# SCH_BOB_Drivers_4x_2022-07-10.net
KiCad netlist of a schematic drawn in EasyEDA
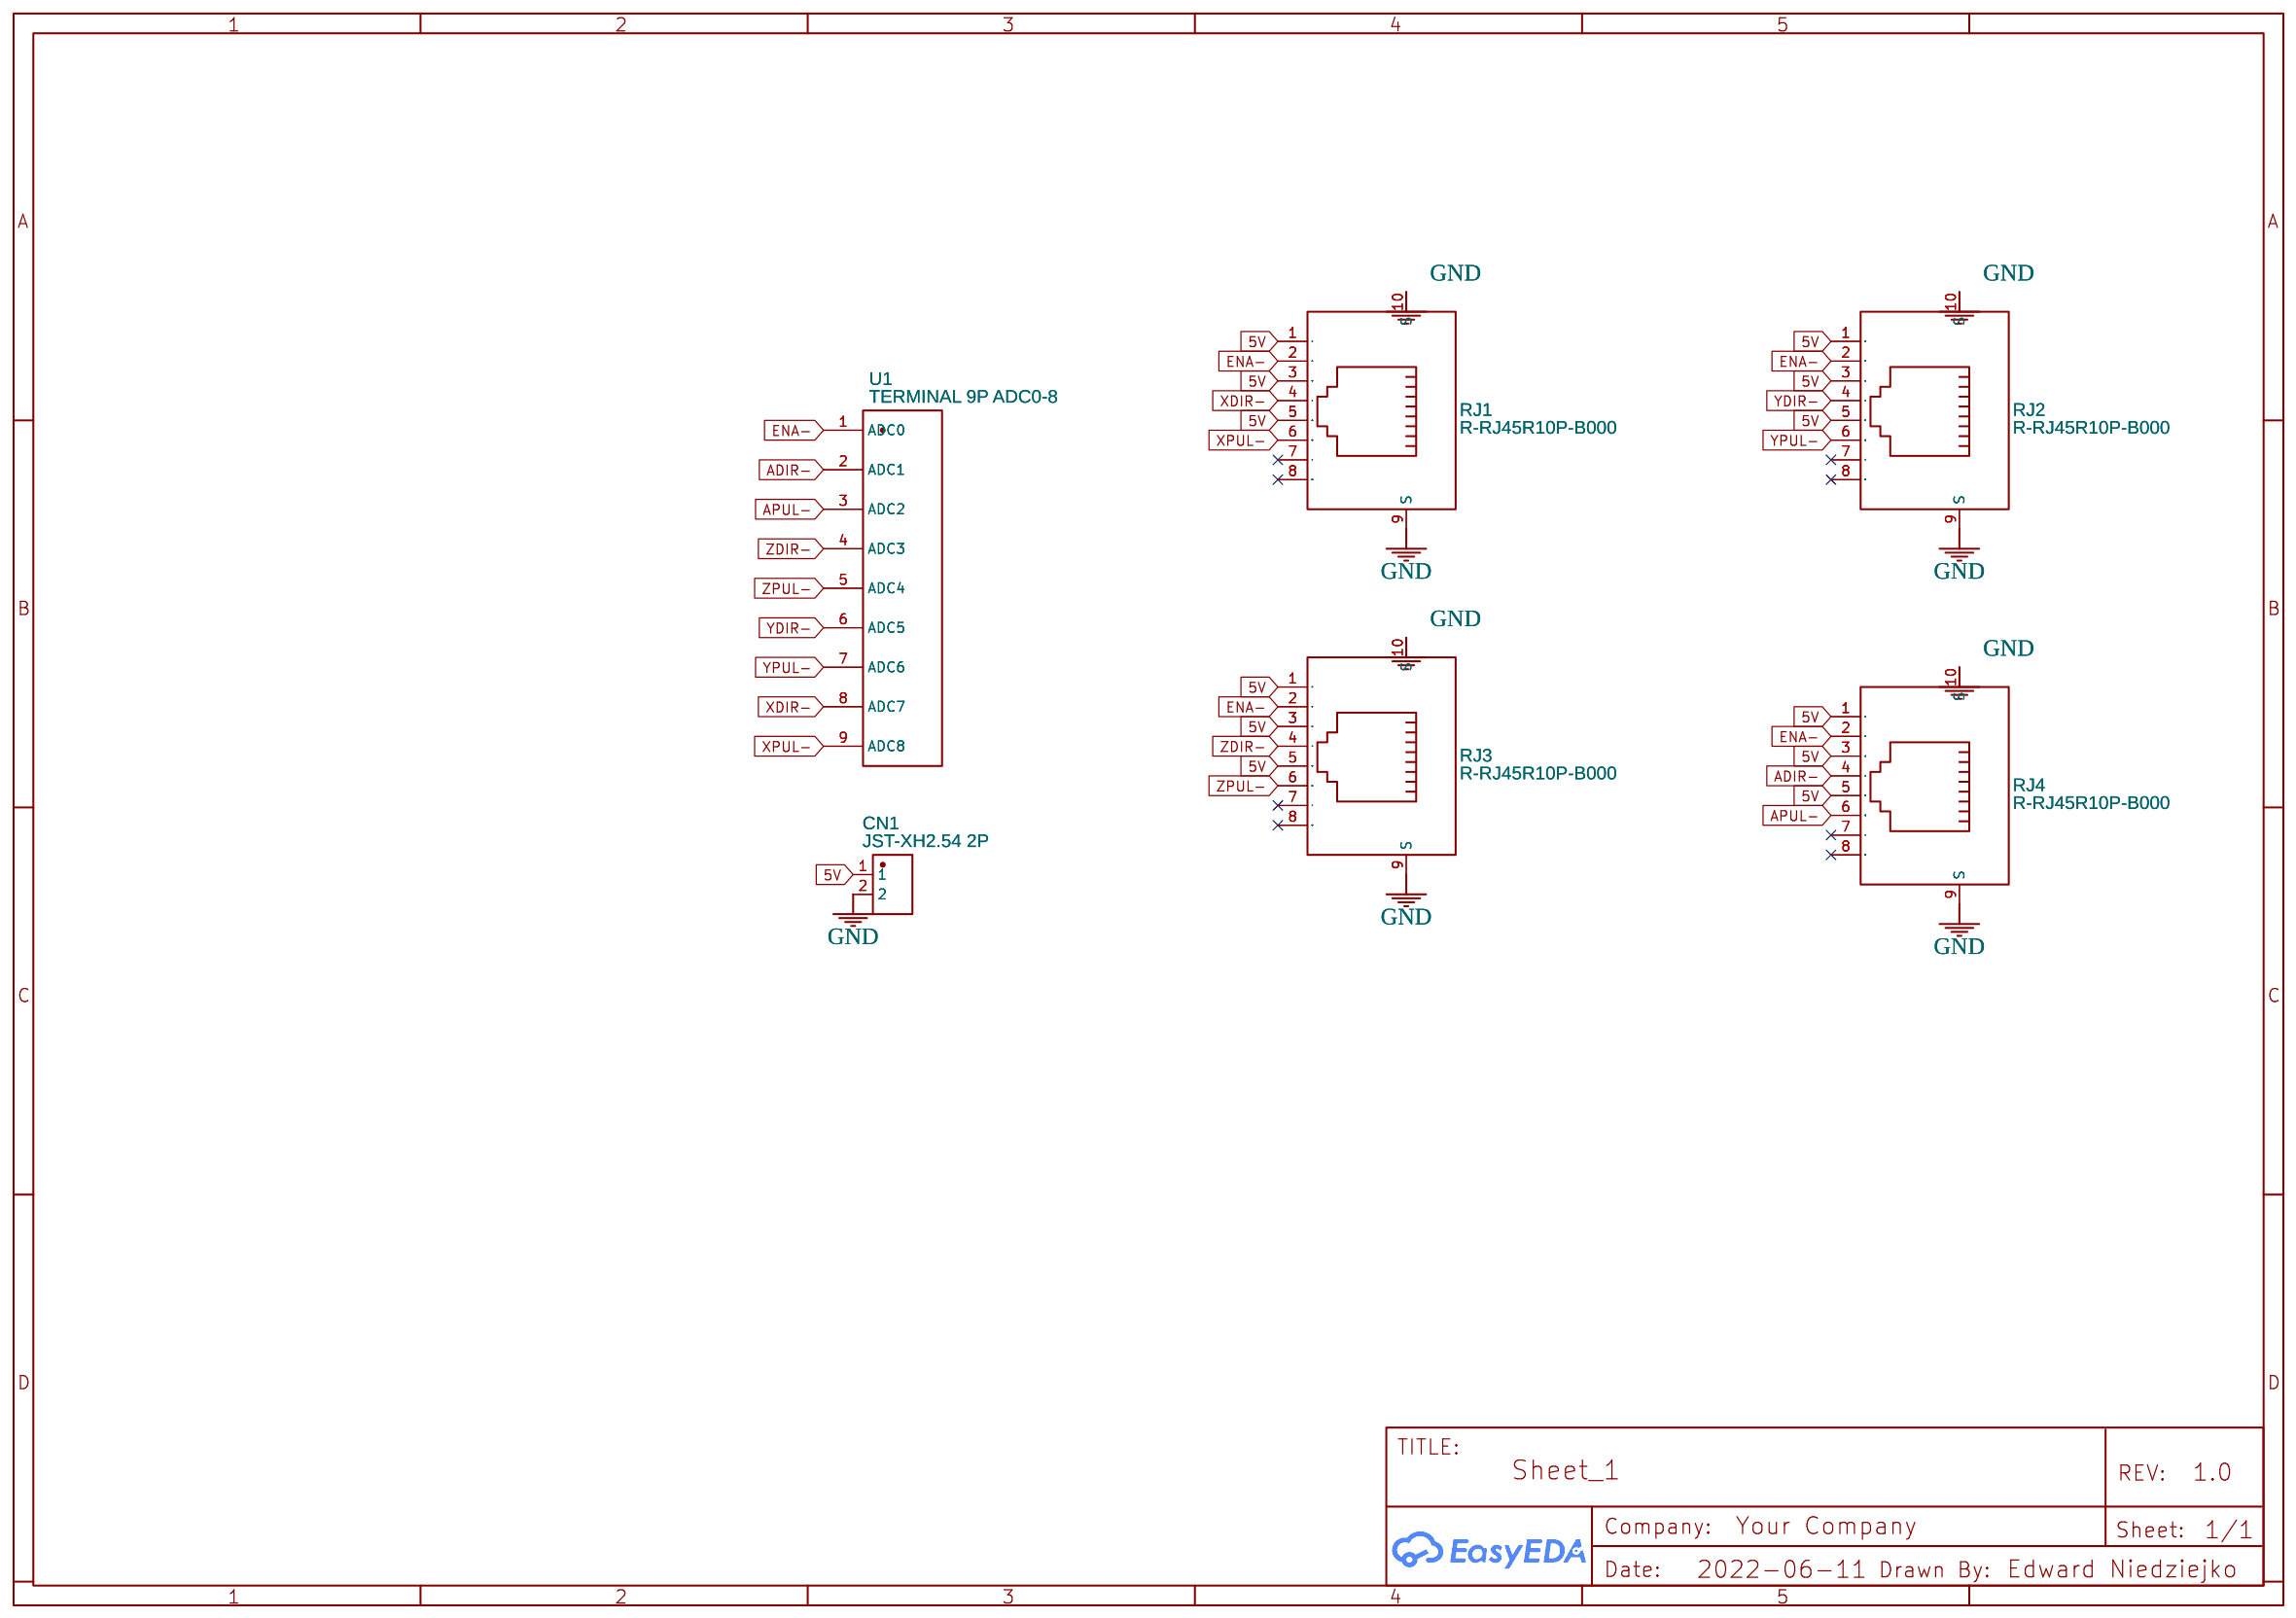
[diagram p0: schematic sheet]

(export (version "E")
  (design (tool "Eeschema 10.0.6"))
  (components
    (comp (ref "CN1") (value "JST-XH2.54 2P") (libsource (lib "") (part "JST-XH2.54 2P")))
    (comp (ref "RJ1")
      (value "R-RJ45R10P-B000")
      (fields (field (name "BOM_Supplier Part") "C386758"))
      (libsource (lib "") (part "R-RJ45R10P-B000"))
    )
    (comp (ref "RJ2")
      (value "R-RJ45R10P-B000")
      (fields (field (name "BOM_Supplier Part") "C386758"))
      (libsource (lib "") (part "R-RJ45R10P-B000"))
    )
    (comp (ref "RJ3")
      (value "R-RJ45R10P-B000")
      (fields (field (name "BOM_Supplier Part") "C386758"))
      (libsource (lib "") (part "R-RJ45R10P-B000"))
    )
    (comp (ref "RJ4")
      (value "R-RJ45R10P-B000")
      (fields (field (name "BOM_Supplier Part") "C386758"))
      (libsource (lib "") (part "R-RJ45R10P-B000"))
    )
    (comp (ref "U1")
      (value "TERMINAL 9P ADC0-8")
      (fields (field (name "BOM_Supplier Part") "KF-301-3P"))
      (libsource (lib "") (part "TERMINAL 9P ADC0-8"))
    )
  )
  (nets
    (net (code "1") (name "5V") (class "Default")
      (node (ref "CN1") (pin "1") (pinfunction "1_1") (pintype "unspecified"))
      (node (ref "RJ1") (pin "1") (pinfunction "1_1") (pintype "unspecified"))
      (node (ref "RJ1") (pin "3") (pinfunction "3_3") (pintype "unspecified"))
      (node (ref "RJ1") (pin "5") (pinfunction "5_5") (pintype "unspecified"))
      (node (ref "RJ2") (pin "1") (pinfunction "1_1") (pintype "unspecified"))
      (node (ref "RJ2") (pin "3") (pinfunction "3_3") (pintype "unspecified"))
      (node (ref "RJ2") (pin "5") (pinfunction "5_5") (pintype "unspecified"))
      (node (ref "RJ3") (pin "1") (pinfunction "1_1") (pintype "unspecified"))
      (node (ref "RJ3") (pin "3") (pinfunction "3_3") (pintype "unspecified"))
      (node (ref "RJ3") (pin "5") (pinfunction "5_5") (pintype "unspecified"))
      (node (ref "RJ4") (pin "1") (pinfunction "1_1") (pintype "unspecified"))
      (node (ref "RJ4") (pin "3") (pinfunction "3_3") (pintype "unspecified"))
      (node (ref "RJ4") (pin "5") (pinfunction "5_5") (pintype "unspecified"))
    )
    (net (code "2") (name "ADIR-") (class "Default")
      (node (ref "RJ4") (pin "4") (pinfunction "4_4") (pintype "unspecified"))
      (node (ref "U1") (pin "2") (pinfunction "ADC1_2") (pintype "unspecified"))
    )
    (net (code "3") (name "APUL-") (class "Default")
      (node (ref "RJ4") (pin "6") (pinfunction "6_6") (pintype "unspecified"))
      (node (ref "U1") (pin "3") (pinfunction "ADC2_3") (pintype "unspecified"))
    )
    (net (code "4") (name "ENA-") (class "Default")
      (node (ref "RJ1") (pin "2") (pinfunction "2_2") (pintype "unspecified"))
      (node (ref "RJ2") (pin "2") (pinfunction "2_2") (pintype "unspecified"))
      (node (ref "RJ3") (pin "2") (pinfunction "2_2") (pintype "unspecified"))
      (node (ref "RJ4") (pin "2") (pinfunction "2_2") (pintype "unspecified"))
      (node (ref "U1") (pin "1") (pinfunction "ADC0_1") (pintype "unspecified"))
    )
    (net (code "5") (name "GND") (class "Default")
      (node (ref "CN1") (pin "2") (pinfunction "2_2") (pintype "unspecified"))
      (node (ref "RJ1") (pin "10") (pinfunction "S_10") (pintype "unspecified"))
      (node (ref "RJ1") (pin "9") (pinfunction "S_9") (pintype "unspecified"))
      (node (ref "RJ2") (pin "10") (pinfunction "S_10") (pintype "unspecified"))
      (node (ref "RJ2") (pin "9") (pinfunction "S_9") (pintype "unspecified"))
      (node (ref "RJ3") (pin "10") (pinfunction "S_10") (pintype "unspecified"))
      (node (ref "RJ3") (pin "9") (pinfunction "S_9") (pintype "unspecified"))
      (node (ref "RJ4") (pin "10") (pinfunction "S_10") (pintype "unspecified"))
      (node (ref "RJ4") (pin "9") (pinfunction "S_9") (pintype "unspecified"))
    )
    (net (code "6") (name "XDIR-") (class "Default")
      (node (ref "RJ1") (pin "4") (pinfunction "4_4") (pintype "unspecified"))
      (node (ref "U1") (pin "8") (pinfunction "ADC7_8") (pintype "unspecified"))
    )
    (net (code "7") (name "XPUL-") (class "Default")
      (node (ref "RJ1") (pin "6") (pinfunction "6_6") (pintype "unspecified"))
      (node (ref "U1") (pin "9") (pinfunction "ADC8_9") (pintype "unspecified"))
    )
    (net (code "8") (name "YDIR-") (class "Default")
      (node (ref "RJ2") (pin "4") (pinfunction "4_4") (pintype "unspecified"))
      (node (ref "U1") (pin "6") (pinfunction "ADC5_6") (pintype "unspecified"))
    )
    (net (code "9") (name "YPUL-") (class "Default")
      (node (ref "RJ2") (pin "6") (pinfunction "6_6") (pintype "unspecified"))
      (node (ref "U1") (pin "7") (pinfunction "ADC6_7") (pintype "unspecified"))
    )
    (net (code "10") (name "ZDIR-") (class "Default")
      (node (ref "RJ3") (pin "4") (pinfunction "4_4") (pintype "unspecified"))
      (node (ref "U1") (pin "4") (pinfunction "ADC3_4") (pintype "unspecified"))
    )
    (net (code "11") (name "ZPUL-") (class "Default")
      (node (ref "RJ3") (pin "6") (pinfunction "6_6") (pintype "unspecified"))
      (node (ref "U1") (pin "5") (pinfunction "ADC4_5") (pintype "unspecified"))
    )
    (net (code "12") (name "unconnected-(RJ1-Pad7)") (class "Default")
      (node (ref "RJ1") (pin "7") (pinfunction "7_7") (pintype "unspecified+no_connect"))
    )
    (net (code "13") (name "unconnected-(RJ1-Pad8)") (class "Default")
      (node (ref "RJ1") (pin "8") (pinfunction "8_8") (pintype "unspecified+no_connect"))
    )
    (net (code "14") (name "unconnected-(RJ2-Pad7)") (class "Default")
      (node (ref "RJ2") (pin "7") (pinfunction "7_7") (pintype "unspecified+no_connect"))
    )
    (net (code "15") (name "unconnected-(RJ2-Pad8)") (class "Default")
      (node (ref "RJ2") (pin "8") (pinfunction "8_8") (pintype "unspecified+no_connect"))
    )
    (net (code "16") (name "unconnected-(RJ3-Pad7)") (class "Default")
      (node (ref "RJ3") (pin "7") (pinfunction "7_7") (pintype "unspecified+no_connect"))
    )
    (net (code "17") (name "unconnected-(RJ3-Pad8)") (class "Default")
      (node (ref "RJ3") (pin "8") (pinfunction "8_8") (pintype "unspecified+no_connect"))
    )
    (net (code "18") (name "unconnected-(RJ4-Pad7)") (class "Default")
      (node (ref "RJ4") (pin "7") (pinfunction "7_7") (pintype "unspecified+no_connect"))
    )
    (net (code "19") (name "unconnected-(RJ4-Pad8)") (class "Default")
      (node (ref "RJ4") (pin "8") (pinfunction "8_8") (pintype "unspecified+no_connect"))
    )
  )
)
